# eye_board.net
KiCad netlist of a schematic drawn in EAGLE
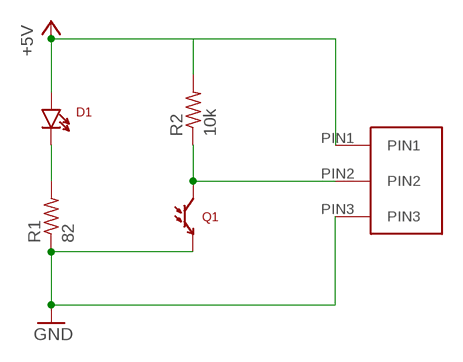
[diagram p0: schematic, sheet 1]

(export (version "E")
  (design (tool "Eeschema 10.0.6"))
  (components
    (comp (ref "3PIN_CONN")
      (value "XH_JST_CONN_3POS_TOP")
      (footprint "eagle-import:XH_JST_CONN_3POS_TOP")
      (libsource (lib "eagle-import") (part "XH_JST_CONN_3POS_TOP"))
    )
    (comp (ref "D1")
      (value "LTE-302")
      (footprint "eagle-import:LTE-302")
      (libsource (lib "eagle-import") (part "LTE-302"))
    )
    (comp (ref "Q1")
      (value "LTR-301")
      (footprint "eagle-import:LTR-301")
      (libsource (lib "eagle-import") (part "LTR-301"))
    )
    (comp (ref "R1")
      (value "82")
      (footprint "eagle-import:R0603")
      (libsource (lib "eagle-import") (part "R-US_R0603"))
    )
    (comp (ref "R2")
      (value "10k")
      (footprint "eagle-import:R0805")
      (libsource (lib "eagle-import") (part "R-US_R0805"))
    )
  )
  (nets
    (net (code "1") (name "+5V") (class "Default")
      (node (ref "3PIN_CONN") (pin "PIN1") (pinfunction "PIN1_PIN1") (pintype "bidirectional"))
      (node (ref "D1") (pin "A") (pinfunction "A_A") (pintype "bidirectional"))
      (node (ref "R2") (pin "2") (pinfunction "2_2") (pintype "passive"))
    )
    (net (code "2") (name "GND") (class "Default")
      (node (ref "3PIN_CONN") (pin "PIN3") (pinfunction "PIN3_PIN3") (pintype "bidirectional"))
      (node (ref "Q1") (pin "E") (pinfunction "E_E") (pintype "bidirectional"))
      (node (ref "R1") (pin "1") (pinfunction "1_1") (pintype "passive"))
    )
    (net (code "3") (name "Net-(3PIN_CONN-PadPIN2)") (class "Default")
      (node (ref "3PIN_CONN") (pin "PIN2") (pinfunction "PIN2_PIN2") (pintype "bidirectional"))
      (node (ref "Q1") (pin "C") (pinfunction "C_C") (pintype "bidirectional"))
      (node (ref "R2") (pin "1") (pinfunction "1_1") (pintype "passive"))
    )
    (net (code "4") (name "Net-(D1-PadC)") (class "Default")
      (node (ref "D1") (pin "C") (pinfunction "C_C") (pintype "bidirectional"))
      (node (ref "R1") (pin "2") (pinfunction "2_2") (pintype "passive"))
    )
  )
)
